# LevelShifter.net
KiCad netlist of a schematic drawn in Altium Designer
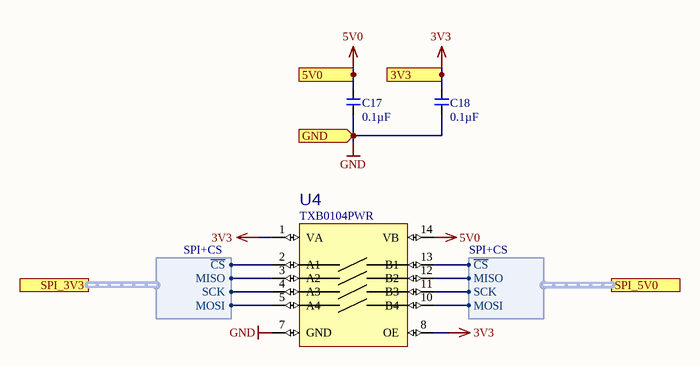
[diagram p0: LevelShifter.SchDoc]

(export (version "E")
  (design (tool "Eeschema 10.0.6"))
  (components
    (comp (ref "C17")
      (value "__template_cap")
      (footprint "C0603")
      (description "CAP CER 0603 0.1µF X7R 50V 10%")
      (fields
        (field (name "CAPACITANCE (SHORTHAND)") "0.1µF")
        (field (name "MANUFACTURER") "Murata Electronics North America")
      )
      (libsource (lib "passives") (part "__template_cap"))
    )
    (comp (ref "C18")
      (value "__template_cap")
      (footprint "C0603")
      (description "CAP CER 0603 0.1µF X7R 50V 10%")
      (fields
        (field (name "CAPACITANCE (SHORTHAND)") "0.1µF")
        (field (name "MANUFACTURER") "Murata Electronics North America")
      )
      (libsource (lib "passives") (part "__template_cap"))
    )
    (comp (ref "U4")
      (value "TXB0104")
      (footprint "14TSSOP65")
      (description "4 Pin Bidirectional levelshifter 5v-3.3v")
      (fields
        (field (name "MANUFACTURER") "Texas Instruments")
        (field (name "MANUFACTURER PART NUMBER") "TXB0104PWR")
      )
      (libsource (lib "SSI") (part "LVLSHFT_TXB0104PWR"))
    )
  )
  (nets
    (net (code "3") (name "3V3") (class "Default")
      (node (ref "C18") (pin "1") (pintype "passive"))
      (node (ref "U4") (pin "1") (pinfunction "VA_1") (pintype "bidirectional"))
      (node (ref "U4") (pin "8") (pinfunction "OE_8") (pintype "bidirectional"))
    )
    (net (code "4") (name "5V0") (class "Default")
      (node (ref "C17") (pin "1") (pintype "passive"))
      (node (ref "U4") (pin "14") (pinfunction "VB_14") (pintype "bidirectional"))
    )
    (net (code "5") (name "GND") (class "Default")
      (node (ref "C17") (pin "2") (pintype "passive"))
      (node (ref "C18") (pin "2") (pintype "passive"))
      (node (ref "U4") (pin "7") (pinfunction "GND_7") (pintype "bidirectional"))
    )
    (net (code "6") (name "unconnected-(U4-A1-Pad2)") (class "Default")
      (node (ref "U4") (pin "2") (pinfunction "A1_2") (pintype "bidirectional"))
    )
    (net (code "7") (name "unconnected-(U4-A2-Pad3)") (class "Default")
      (node (ref "U4") (pin "3") (pinfunction "A2_3") (pintype "bidirectional"))
    )
    (net (code "8") (name "unconnected-(U4-A3-Pad4)") (class "Default")
      (node (ref "U4") (pin "4") (pinfunction "A3_4") (pintype "bidirectional"))
    )
    (net (code "9") (name "unconnected-(U4-A4-Pad5)") (class "Default")
      (node (ref "U4") (pin "5") (pinfunction "A4_5") (pintype "bidirectional"))
    )
    (net (code "10") (name "unconnected-(U4-B1-Pad13)") (class "Default")
      (node (ref "U4") (pin "13") (pinfunction "B1_13") (pintype "bidirectional"))
    )
    (net (code "11") (name "unconnected-(U4-B2-Pad12)") (class "Default")
      (node (ref "U4") (pin "12") (pinfunction "B2_12") (pintype "bidirectional"))
    )
    (net (code "12") (name "unconnected-(U4-B3-Pad11)") (class "Default")
      (node (ref "U4") (pin "11") (pinfunction "B3_11") (pintype "bidirectional"))
    )
    (net (code "13") (name "unconnected-(U4-B4-Pad10)") (class "Default")
      (node (ref "U4") (pin "10") (pinfunction "B4_10") (pintype "bidirectional"))
    )
  )
)
